# powerA.net
KiCad netlist of a schematic drawn in Altium Designer
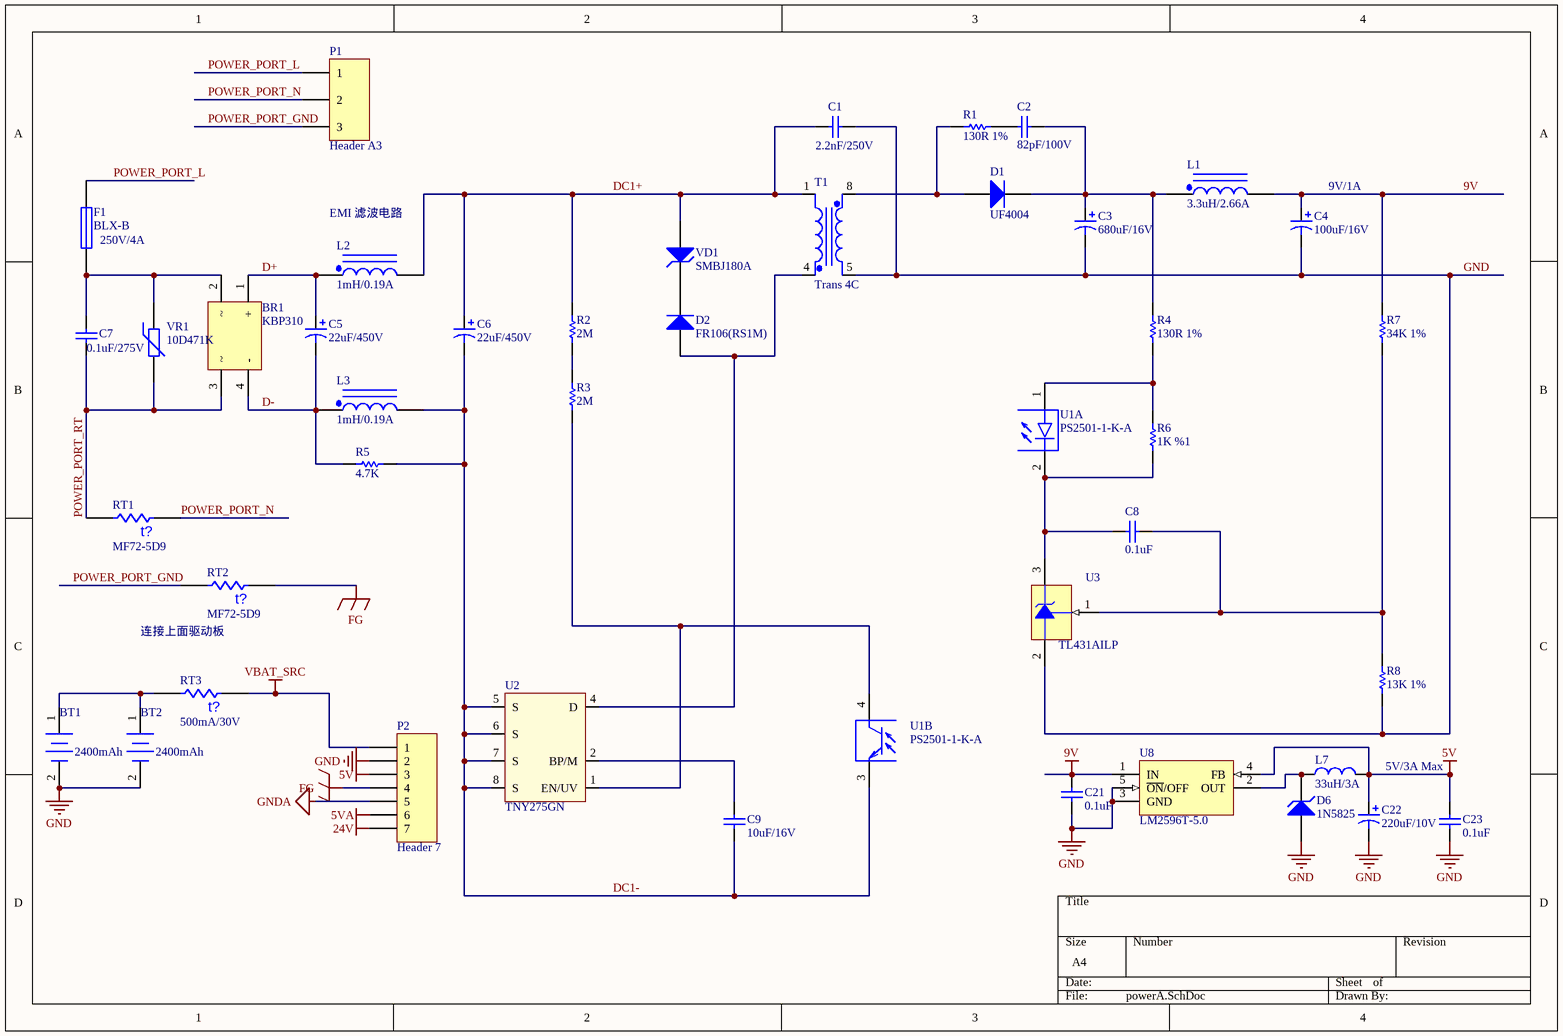
[diagram p0: powerA.SchDoc]

(export (version "E")
  (design (tool "Eeschema 10.0.6"))
  (components
    (comp (ref "BR1")
      (value "KBP310")
      (footprint "BRD1")
      (description "AC-DC Bridge")
      (libsource (lib "UserSchDev") (part "KP210"))
    )
    (comp (ref "BT1")
      (value "2400mAh")
      (footprint "BAT-14500")
      (description "Battery holder")
      (fields (field (name "PUBLISHER") "Altium Limited"))
      (libsource (lib "Miscellaneous Devices") (part "Battery"))
    )
    (comp (ref "BT2")
      (value "2400mAh")
      (footprint "BAT-14500")
      (description "Battery holder")
      (fields (field (name "PUBLISHER") "Altium Limited"))
      (libsource (lib "Miscellaneous Devices") (part "Battery"))
    )
    (comp (ref "C1")
      (value "2.2nF/250V")
      (footprint "CAPRD5-9x3B")
      (description "Capacitor")
      (fields (field (name "PUBLISHER") "Altium Limited"))
      (libsource (lib "Miscellaneous Devices") (part "Cap"))
    )
    (comp (ref "C2")
      (value "82pF/100V")
      (footprint "CAPC3216M")
      (description "Capacitor")
      (fields (field (name "PUBLISHER") "Altium Limited"))
      (libsource (lib "Miscellaneous Devices") (part "Cap"))
    )
    (comp (ref "C3")
      (value "680uF/16V")
      (footprint "CAPPR2.5-8x12")
      (description "Polarized Capacitor (Radial)")
      (fields (field (name "PUBLISHER") "Altium Limited"))
      (libsource (lib "Miscellaneous Devices") (part "Cap Pol1"))
    )
    (comp (ref "C4")
      (value "100uF/16V")
      (footprint "CAPPR2-5x7")
      (description "Polarized Capacitor (Radial)")
      (fields (field (name "PUBLISHER") "Altium Limited"))
      (libsource (lib "Miscellaneous Devices") (part "Cap Pol1"))
    )
    (comp (ref "C5")
      (value "22uF/450V")
      (footprint "CAPPR7.5-16x25B")
      (description "Polarized Capacitor (Radial)")
      (fields (field (name "PUBLISHER") "Altium Limited"))
      (libsource (lib "Miscellaneous Devices") (part "Cap Pol1"))
    )
    (comp (ref "C6")
      (value "22uF/450V")
      (footprint "CAPPR7.5-16x25B")
      (description "Polarized Capacitor (Radial)")
      (fields (field (name "PUBLISHER") "Altium Limited"))
      (libsource (lib "Miscellaneous Devices") (part "Cap Pol1"))
    )
    (comp (ref "C7")
      (value "0.1uF/275V")
      (footprint "CAPRD10-12x6")
      (description "Capacitor")
      (fields (field (name "PUBLISHER") "Altium Limited"))
      (libsource (lib "Miscellaneous Devices") (part "Cap"))
    )
    (comp (ref "C8")
      (value "0.1uF")
      (footprint "CAPC3216M")
      (description "Capacitor")
      (fields (field (name "PUBLISHER") "Altium Limited"))
      (libsource (lib "Miscellaneous Devices") (part "Cap"))
    )
    (comp (ref "C9")
      (value "10uF/16V")
      (footprint "CAPC3216M")
      (description "Capacitor")
      (fields (field (name "PUBLISHER") "Altium Limited"))
      (libsource (lib "Miscellaneous Devices") (part "Cap"))
    )
    (comp (ref "C21")
      (value "0.1uF")
      (footprint "CAPC3216M")
      (description "Capacitor")
      (fields (field (name "PUBLISHER") "Altium Limited"))
      (libsource (lib "Miscellaneous Devices") (part "Cap"))
    )
    (comp (ref "C22")
      (value "220uF/10V")
      (footprint "CAPPR2.5-6.3x11.5")
      (description "Polarized Capacitor (Radial)")
      (fields (field (name "PUBLISHER") "Altium Limited"))
      (libsource (lib "Miscellaneous Devices") (part "Cap Pol1"))
    )
    (comp (ref "C23")
      (value "0.1uF")
      (footprint "CAPC3216M")
      (description "Capacitor")
      (fields (field (name "PUBLISHER") "Altium Limited"))
      (libsource (lib "Miscellaneous Devices") (part "Cap"))
    )
    (comp (ref "D1")
      (value "UF4004")
      (footprint "SMA")
      (description "High Conductance Fast Diode")
      (fields (field (name "PUBLISHER") "Altium Limited"))
      (libsource (lib "Miscellaneous Devices") (part "Diode 1N4148"))
    )
    (comp (ref "D2")
      (value "FR106(RS1M)")
      (footprint "SMA")
      (description "High Conductance Fast Diode")
      (fields (field (name "PUBLISHER") "Altium Limited"))
      (libsource (lib "Miscellaneous Devices") (part "Diode 1N4148"))
    )
    (comp (ref "D6")
      (value "1N5825")
      (footprint "SMB")
      (description "Zener Diode")
      (fields (field (name "PUBLISHER") "Altium Limited"))
      (libsource (lib "Miscellaneous Devices") (part "D Zener"))
    )
    (comp (ref "F1")
      (value "BLX-B")
      (footprint "FUSE22")
      (description "Fuse Holder 25mm(L)x10mm(W)x13mm(H)")
      (fields (field (name "PUBLISHER") "Altium Limited"))
      (libsource (lib "Miscellaneous Devices") (part "Fuse 1"))
    )
    (comp (ref "L1")
      (value "3.3uH/2.66A")
      (footprint "L0810")
      (description "Magnetic-Core Inductor with Winding Polarity Marking")
      (fields (field (name "PUBLISHER") "Altium Limited"))
      (libsource (lib "Miscellaneous Devices") (part "Inductor Iron Dot"))
    )
    (comp (ref "L2")
      (value "1mH/0.19A")
      (footprint "L0810")
      (description "Magnetic-Core Inductor with Winding Polarity Marking")
      (fields (field (name "PUBLISHER") "Altium Limited"))
      (libsource (lib "Miscellaneous Devices") (part "Inductor Iron Dot"))
    )
    (comp (ref "L3")
      (value "1mH/0.19A")
      (footprint "L0810")
      (description "Magnetic-Core Inductor with Winding Polarity Marking")
      (fields (field (name "PUBLISHER") "Altium Limited"))
      (libsource (lib "Miscellaneous Devices") (part "Inductor Iron Dot"))
    )
    (comp (ref "L7")
      (value "33uH/3A")
      (footprint "L0810")
      (description "Inductor with Winding No Polarity Marking")
      (fields (field (name "PUBLISHER") "Altium Limited"))
      (libsource (lib "UserLib") (part "Inductor"))
    )
    (comp (ref "P1")
      (value "Header A3")
      (footprint "DG500HH-5.08-3")
      (description "Header, 3-Pin")
      (fields (field (name "PUBLISHER") "Altium Limited"))
      (libsource (lib "UserSchCon") (part "Header A3"))
    )
    (comp (ref "P2")
      (value "Header 7")
      (footprint "HDR1X7")
      (description "Header, 7-Pin")
      (fields (field (name "PUBLISHER") "Altium Limited"))
      (libsource (lib "UserSchCon") (part "Header 7"))
    )
    (comp (ref "R1")
      (value "130R 1%")
      (footprint "RESC3216M")
      (description "Metal film Resistor")
      (fields (field (name "PUBLISHER") "Altium Limited"))
      (libsource (lib "Miscellaneous Devices") (part "Res Semi"))
    )
    (comp (ref "R2")
      (value "2M")
      (footprint "RESC3216M")
      (description "Metal film Resistor")
      (fields (field (name "PUBLISHER") "Altium Limited"))
      (libsource (lib "Miscellaneous Devices") (part "Res Semi"))
    )
    (comp (ref "R3")
      (value "2M")
      (footprint "RESC3216M")
      (description "Metal film Resistor")
      (fields (field (name "PUBLISHER") "Altium Limited"))
      (libsource (lib "Miscellaneous Devices") (part "Res Semi"))
    )
    (comp (ref "R4")
      (value "130R 1%")
      (footprint "RESC3216M")
      (description "Metal film Resistor")
      (fields (field (name "PUBLISHER") "Altium Limited"))
      (libsource (lib "Miscellaneous Devices") (part "Res Semi"))
    )
    (comp (ref "R5")
      (value "4.7K")
      (footprint "RESC3216M")
      (description "Metal film Resistor")
      (fields (field (name "PUBLISHER") "Altium Limited"))
      (libsource (lib "Miscellaneous Devices") (part "Res Semi"))
    )
    (comp (ref "R6")
      (value "1K %1")
      (footprint "RESC3216M")
      (description "Metal film Resistor")
      (fields (field (name "PUBLISHER") "Altium Limited"))
      (libsource (lib "Miscellaneous Devices") (part "Res Semi"))
    )
    (comp (ref "R7")
      (value "34K 1%")
      (footprint "RESC3216M")
      (description "Metal film Resistor")
      (fields (field (name "PUBLISHER") "Altium Limited"))
      (libsource (lib "Miscellaneous Devices") (part "Res Semi"))
    )
    (comp (ref "R8")
      (value "13K 1%")
      (footprint "RESC3216M")
      (description "Metal film Resistor")
      (fields (field (name "PUBLISHER") "Altium Limited"))
      (libsource (lib "Miscellaneous Devices") (part "Res Semi"))
    )
    (comp (ref "RT1")
      (value "MF72-5D9")
      (footprint "CAPRD7.5-11x4A")
      (description "Thermistor")
      (fields (field (name "PUBLISHER") "Altium Limited"))
      (libsource (lib "Miscellaneous Devices") (part "Res Thermal"))
    )
    (comp (ref "RT2")
      (value "MF72-5D9")
      (footprint "CAPRD7.5-11x4A")
      (description "Thermistor")
      (fields (field (name "PUBLISHER") "Altium Limited"))
      (libsource (lib "Miscellaneous Devices") (part "Res Thermal"))
    )
    (comp (ref "RT3")
      (value "500mA/30V")
      (footprint "RESC3216M")
      (description "Thermistor")
      (fields (field (name "PUBLISHER") "Altium Limited"))
      (libsource (lib "Miscellaneous Devices") (part "Res Thermal"))
    )
    (comp (ref "T1")
      (value "Trans 4C")
      (footprint "EE19W(2+2)")
      (description "Transformer")
      (fields (field (name "PUBLISHER") "Altium Limited"))
      (libsource (lib "UserSchDev") (part "Trans 4C"))
    )
    (comp (ref "U1")
      (value "PS2501-1-K-A")
      (footprint "SOP-4")
      (description "Single-Supply Dual Operational Amplifier,10MHz")
      (fields (field (name "PUBLISHER") "Altium Limited"))
      (libsource (lib "UserLib") (part "PC817D"))
    )
    (comp (ref "U2") (value "TNY275GN") (footprint "SMD-8C") (libsource (lib "UserLib") (part "TNY279PN")))
    (comp (ref "U3")
      (value "TL431AILP")
      (footprint "TO-92AA")
      (description "Programmable Precision Reference")
      (fields (field (name "PUBLISHER") "Altium Limited"))
      (libsource (lib "ON Semi Power Mgt Voltage Reference") (part "TL431CLP"))
    )
    (comp (ref "U8")
      (value "LM2596T-5.0")
      (footprint "TO-220-5")
      (description "5V稳压芯片")
      (fields (field (name "PUBLISHER") "Altium Limited"))
      (libsource (lib "UserSchDev") (part "LM2596T-5.0"))
    )
    (comp (ref "VD1")
      (value "SMBJ180A")
      (footprint "SMB")
      (description "Zener Diode")
      (fields (field (name "PUBLISHER") "Altium Limited"))
      (libsource (lib "Miscellaneous Devices") (part "D Zener"))
    )
    (comp (ref "VR1")
      (value "10D471K")
      (footprint "CAPRD7.5-7x4C")
      (description "Varistor (Voltage-Sensitive Resistor)")
      (fields (field (name "PUBLISHER") "Altium Limited"))
      (libsource (lib "Miscellaneous Devices") (part "Res Varistor"))
    )
  )
  (nets
    (net (code "1") (name "/D+") (class "Default")
      (node (ref "BR1") (pin "1") (pinfunction "+_1") (pintype "power_in"))
      (node (ref "C5") (pin "1") (pinfunction "1_1") (pintype "passive"))
      (node (ref "L2") (pin "1") (pinfunction "1_1") (pintype "passive"))
    )
    (net (code "2") (name "/D-") (class "Default")
      (node (ref "BR1") (pin "4") (pinfunction "-_4") (pintype "power_in"))
      (node (ref "C5") (pin "2") (pinfunction "2_2") (pintype "passive"))
      (node (ref "L3") (pin "1") (pinfunction "1_1") (pintype "passive"))
      (node (ref "R5") (pin "2") (pinfunction "2_2") (pintype "passive"))
    )
    (net (code "3") (name "/DC1+") (class "Default")
      (node (ref "C1") (pin "1") (pinfunction "1_1") (pintype "passive"))
      (node (ref "C6") (pin "1") (pinfunction "1_1") (pintype "passive"))
      (node (ref "L2") (pin "2") (pinfunction "2_2") (pintype "passive"))
      (node (ref "R2") (pin "2") (pinfunction "2_2") (pintype "passive"))
      (node (ref "T1") (pin "1") (pinfunction "Pri+_1") (pintype "passive"))
      (node (ref "VD1") (pin "1") (pinfunction "A_1") (pintype "passive"))
    )
    (net (code "4") (name "/DC1-") (class "Default")
      (node (ref "C6") (pin "2") (pinfunction "2_2") (pintype "passive"))
      (node (ref "C9") (pin "2") (pinfunction "2_2") (pintype "passive"))
      (node (ref "L3") (pin "2") (pinfunction "2_2") (pintype "passive"))
      (node (ref "R5") (pin "1") (pinfunction "1_1") (pintype "passive"))
      (node (ref "U1") (pin "3") (pinfunction "E_3") (pintype "passive"))
      (node (ref "U2") (pin "5") (pinfunction "S_5") (pintype "passive"))
      (node (ref "U2") (pin "6") (pinfunction "S_6") (pintype "passive"))
      (node (ref "U2") (pin "7") (pinfunction "S_7") (pintype "passive"))
      (node (ref "U2") (pin "8") (pinfunction "S_8") (pintype "passive"))
    )
    (net (code "5") (name "/POWER_PORT_GND") (class "Default")
      (node (ref "P1") (pin "3") (pinfunction "3_3") (pintype "passive"))
      (node (ref "RT2") (pin "2") (pinfunction "2_2") (pintype "passive"))
    )
    (net (code "6") (name "/POWER_PORT_L") (class "Default")
      (node (ref "F1") (pin "1") (pinfunction "1_1") (pintype "passive"))
      (node (ref "P1") (pin "1") (pinfunction "1_1") (pintype "passive"))
    )
    (net (code "7") (name "/POWER_PORT_N") (class "Default")
      (node (ref "P1") (pin "2") (pinfunction "2_2") (pintype "passive"))
      (node (ref "RT1") (pin "1") (pinfunction "1_1") (pintype "passive"))
    )
    (net (code "8") (name "/POWER_PORT_RT") (class "Default")
      (node (ref "BR1") (pin "3") (pinfunction "~_3") (pintype "power_in"))
      (node (ref "C7") (pin "1") (pinfunction "1_1") (pintype "passive"))
      (node (ref "RT1") (pin "2") (pinfunction "2_2") (pintype "passive"))
      (node (ref "VR1") (pin "2") (pinfunction "2_2") (pintype "passive"))
    )
    (net (code "9") (name "5V") (class "Default")
      (node (ref "C22") (pin "1") (pinfunction "1_1") (pintype "passive"))
      (node (ref "C23") (pin "2") (pinfunction "2_2") (pintype "passive"))
      (node (ref "L7") (pin "2") (pinfunction "2_2") (pintype "passive"))
      (node (ref "P2") (pin "3") (pinfunction "3_3") (pintype "passive"))
      (node (ref "U8") (pin "4") (pinfunction "FB_4") (pintype "input"))
    )
    (net (code "10") (name "5VA") (class "Default")
      (node (ref "P2") (pin "6") (pinfunction "6_6") (pintype "passive"))
    )
    (net (code "11") (name "9V") (class "Default")
      (node (ref "C21") (pin "1") (pinfunction "1_1") (pintype "passive"))
      (node (ref "C4") (pin "1") (pinfunction "1_1") (pintype "passive"))
      (node (ref "L1") (pin "2") (pinfunction "2_2") (pintype "passive"))
      (node (ref "R7") (pin "2") (pinfunction "2_2") (pintype "passive"))
      (node (ref "U8") (pin "1") (pinfunction "IN_1") (pintype "power_in"))
    )
    (net (code "12") (name "24V") (class "Default")
      (node (ref "P2") (pin "7") (pinfunction "7_7") (pintype "passive"))
    )
    (net (code "13") (name "FG") (class "Default")
      (node (ref "P2") (pin "4") (pinfunction "4_4") (pintype "passive"))
      (node (ref "RT2") (pin "1") (pinfunction "1_1") (pintype "passive"))
    )
    (net (code "14") (name "GND") (class "Default")
      (node (ref "BT1") (pin "2") (pinfunction "-_2") (pintype "passive"))
      (node (ref "BT2") (pin "2") (pinfunction "-_2") (pintype "passive"))
      (node (ref "C1") (pin "2") (pinfunction "2_2") (pintype "passive"))
      (node (ref "C21") (pin "2") (pinfunction "2_2") (pintype "passive"))
      (node (ref "C22") (pin "2") (pinfunction "2_2") (pintype "passive"))
      (node (ref "C23") (pin "1") (pinfunction "1_1") (pintype "passive"))
      (node (ref "C3") (pin "2") (pinfunction "2_2") (pintype "passive"))
      (node (ref "C4") (pin "2") (pinfunction "2_2") (pintype "passive"))
      (node (ref "D6") (pin "1") (pinfunction "A_1") (pintype "passive"))
      (node (ref "P2") (pin "2") (pinfunction "2_2") (pintype "passive"))
      (node (ref "R8") (pin "1") (pinfunction "1_1") (pintype "passive"))
      (node (ref "T1") (pin "5") (pinfunction "Sec-_5") (pintype "passive"))
      (node (ref "U3") (pin "2") (pinfunction "A_2") (pintype "passive"))
      (node (ref "U8") (pin "3") (pinfunction "GND_3") (pintype "power_in"))
      (node (ref "U8") (pin "5") (pinfunction "~{ON}/OFF_5") (pintype "input"))
    )
    (net (code "15") (name "GNDA") (class "Default")
      (node (ref "P2") (pin "5") (pinfunction "5_5") (pintype "passive"))
    )
    (net (code "16") (name "Net-(BR1-~-Pad2)") (class "Default")
      (node (ref "BR1") (pin "2") (pinfunction "~_2") (pintype "power_in"))
      (node (ref "C7") (pin "2") (pinfunction "2_2") (pintype "passive"))
      (node (ref "F1") (pin "2") (pinfunction "2_2") (pintype "passive"))
      (node (ref "VR1") (pin "1") (pinfunction "1_1") (pintype "passive"))
    )
    (net (code "17") (name "Net-(BT1-+)") (class "Default")
      (node (ref "BT1") (pin "1") (pinfunction "+_1") (pintype "passive"))
      (node (ref "BT2") (pin "1") (pinfunction "+_1") (pintype "passive"))
      (node (ref "RT3") (pin "2") (pinfunction "2_2") (pintype "passive"))
    )
    (net (code "18") (name "Net-(C2-Pad2)") (class "Default")
      (node (ref "C2") (pin "2") (pinfunction "2_2") (pintype "passive"))
      (node (ref "R1") (pin "1") (pinfunction "1_1") (pintype "passive"))
    )
    (net (code "19") (name "Net-(D1-A)") (class "Default")
      (node (ref "D1") (pin "1") (pinfunction "A_1") (pintype "passive"))
      (node (ref "R1") (pin "2") (pinfunction "2_2") (pintype "passive"))
      (node (ref "T1") (pin "8") (pinfunction "Sec+_8") (pintype "passive"))
    )
    (net (code "20") (name "Net-(D1-K)") (class "Default")
      (node (ref "C2") (pin "1") (pinfunction "1_1") (pintype "passive"))
      (node (ref "C3") (pin "1") (pinfunction "1_1") (pintype "passive"))
      (node (ref "D1") (pin "2") (pinfunction "K_2") (pintype "passive"))
      (node (ref "L1") (pin "1") (pinfunction "1_1") (pintype "passive"))
      (node (ref "R4") (pin "2") (pinfunction "2_2") (pintype "passive"))
    )
    (net (code "21") (name "Net-(D2-A)") (class "Default")
      (node (ref "D2") (pin "1") (pinfunction "A_1") (pintype "passive"))
      (node (ref "T1") (pin "4") (pinfunction "Pri-_4") (pintype "passive"))
      (node (ref "U2") (pin "4") (pinfunction "D_4") (pintype "passive"))
    )
    (net (code "22") (name "Net-(D2-K)") (class "Default")
      (node (ref "D2") (pin "2") (pinfunction "K_2") (pintype "passive"))
      (node (ref "VD1") (pin "2") (pinfunction "K_2") (pintype "passive"))
    )
    (net (code "23") (name "Net-(D6-K)") (class "Default")
      (node (ref "D6") (pin "2") (pinfunction "K_2") (pintype "passive"))
      (node (ref "L7") (pin "1") (pinfunction "1_1") (pintype "passive"))
      (node (ref "U8") (pin "2") (pinfunction "OUT_2") (pintype "power_in"))
    )
    (net (code "24") (name "Net-(R2-Pad1)") (class "Default")
      (node (ref "R2") (pin "1") (pinfunction "1_1") (pintype "passive"))
      (node (ref "R3") (pin "1") (pinfunction "1_1") (pintype "passive"))
    )
    (net (code "25") (name "Net-(U1A-+)") (class "Default")
      (node (ref "R4") (pin "1") (pinfunction "1_1") (pintype "passive"))
      (node (ref "R6") (pin "2") (pinfunction "2_2") (pintype "passive"))
      (node (ref "U1") (pin "1") (pinfunction "+_1") (pintype "passive"))
    )
    (net (code "26") (name "Net-(U1A--)") (class "Default")
      (node (ref "C8") (pin "2") (pinfunction "2_2") (pintype "passive"))
      (node (ref "R6") (pin "1") (pinfunction "1_1") (pintype "passive"))
      (node (ref "U1") (pin "2") (pinfunction "-_2") (pintype "passive"))
      (node (ref "U3") (pin "3") (pinfunction "K_3") (pintype "passive"))
    )
    (net (code "27") (name "Net-(U1B-C)") (class "Default")
      (node (ref "R3") (pin "2") (pinfunction "2_2") (pintype "passive"))
      (node (ref "U1") (pin "4") (pinfunction "C_4") (pintype "passive"))
      (node (ref "U2") (pin "1") (pinfunction "EN/UV_1") (pintype "passive"))
    )
    (net (code "28") (name "Net-(U2-BP{slash}M)") (class "Default")
      (node (ref "C9") (pin "1") (pinfunction "1_1") (pintype "passive"))
      (node (ref "U2") (pin "2") (pinfunction "BP/M_2") (pintype "passive"))
    )
    (net (code "29") (name "Net-(U3-REF)") (class "Default")
      (node (ref "C8") (pin "1") (pinfunction "1_1") (pintype "passive"))
      (node (ref "R7") (pin "1") (pinfunction "1_1") (pintype "passive"))
      (node (ref "R8") (pin "2") (pinfunction "2_2") (pintype "passive"))
      (node (ref "U3") (pin "1") (pinfunction "REF_1") (pintype "input"))
    )
    (net (code "30") (name "VBAT_SRC") (class "Default")
      (node (ref "P2") (pin "1") (pinfunction "1_1") (pintype "passive"))
      (node (ref "RT3") (pin "1") (pinfunction "1_1") (pintype "passive"))
    )
  )
)
